# nguyen_ly.net
KiCad netlist of a schematic drawn in Altium Designer
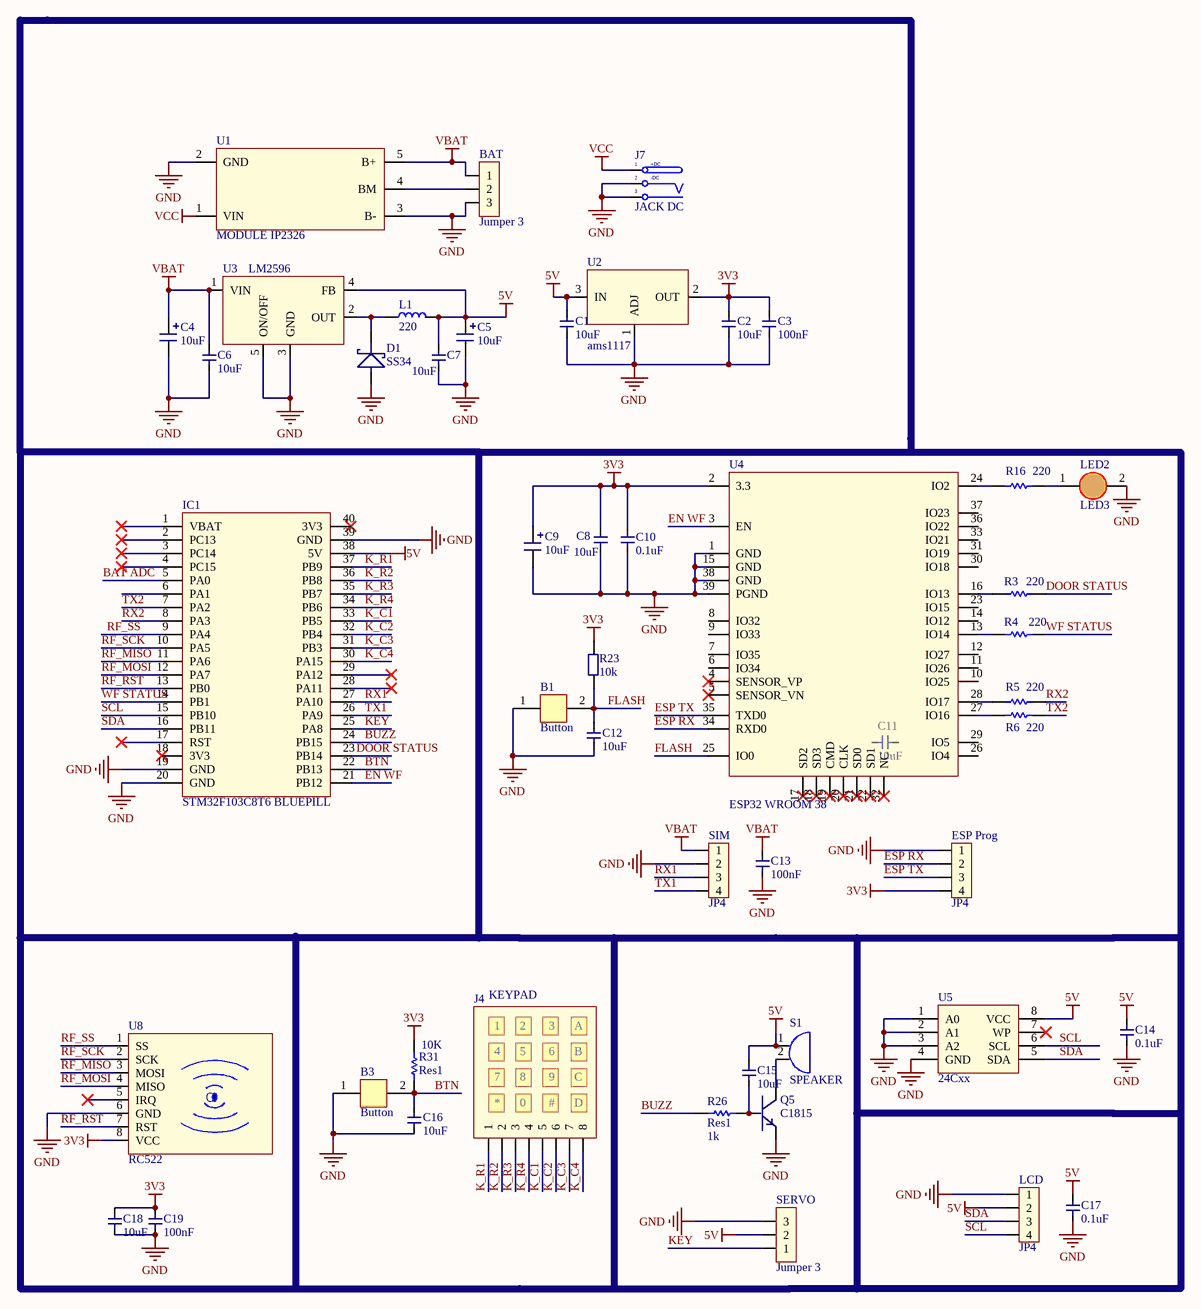
[diagram p0: nguyen_ly.SchDoc]

(export (version "E")
  (design (tool "Eeschema 10.0.6"))
  (components
    (comp (ref "B1")
      (value "Button")
      (footprint "Button 2 Pin")
      (description "Button 2 pin")
      (libsource (lib "Cty1") (part "Button 2 Pin"))
    )
    (comp (ref "B3")
      (value "Button")
      (footprint "Button 2 Pin")
      (description "Button 2 pin")
      (libsource (lib "Cty1") (part "Button 2 Pin"))
    )
    (comp (ref "BAT") (value "Jumper 3") (footprint "JP3") (libsource (lib "") (part "JP3_1")))
    (comp (ref "C1") (value "10uF") (footprint "cap 0805") (libsource (lib "Schlib1") (part "cap")))
    (comp (ref "C2") (value "10uF") (footprint "cap 0805") (libsource (lib "Schlib1") (part "cap")))
    (comp (ref "C3") (value "100nF") (footprint "cap 0805") (libsource (lib "Schlib1") (part "cap")))
    (comp (ref "C4") (value "10uF") (footprint "cap pol 63x54") (libsource (lib "Schlib1") (part "cap pol")))
    (comp (ref "C5") (value "10uF") (footprint "cap pol 63x54") (libsource (lib "Schlib1") (part "cap pol")))
    (comp (ref "C6") (value "10uF") (footprint "cap 0805") (libsource (lib "Schlib1") (part "cap")))
    (comp (ref "C7") (value "10uF") (footprint "cap 0805") (libsource (lib "Schlib1") (part "cap")))
    (comp (ref "C8") (value "10uF") (footprint "cap 0805") (libsource (lib "Schlib1") (part "cap")))
    (comp (ref "C9") (value "10uF") (footprint "cap pol 63x54") (libsource (lib "Schlib1") (part "cap pol")))
    (comp (ref "C10") (value "0.1uF") (footprint "cap 0805") (libsource (lib "Schlib1") (part "cap")))
    (comp (ref "C11") (value "10uF") (footprint "cap 0805") (libsource (lib "Schlib1") (part "cap")))
    (comp (ref "C12") (value "10uF") (footprint "cap 0805") (libsource (lib "Schlib1") (part "cap")))
    (comp (ref "C13") (value "100nF") (footprint "cap 0805") (libsource (lib "Schlib1") (part "cap")))
    (comp (ref "C14") (value "0.1uF") (footprint "cap 0805") (libsource (lib "Schlib1") (part "cap")))
    (comp (ref "C15") (value "10uF") (footprint "cap 0805") (libsource (lib "Schlib1") (part "cap")))
    (comp (ref "C16") (value "10uF") (footprint "cap 0805") (libsource (lib "Schlib1") (part "cap")))
    (comp (ref "C17") (value "0.1uF") (footprint "cap 0805") (libsource (lib "Schlib1") (part "cap")))
    (comp (ref "C18") (value "10uF") (footprint "cap 0805") (libsource (lib "Schlib1") (part "cap")))
    (comp (ref "C19") (value "100nF") (footprint "cap 0805") (libsource (lib "Schlib1") (part "cap")))
    (comp (ref "D1") (value "SS34") (footprint "Diode SS34") (libsource (lib "Schlib1") (part "SS34")))
    (comp (ref "ESP Prog") (value "JP4") (footprint "JP4") (libsource (lib "Schlib1") (part "JP4")))
    (comp (ref "IC1")
      (value "STM32F103C8T6 BLUEPILL")
      (footprint "STM32 BLUEPILL")
      (libsource (lib "Schlib1") (part "STM32F103C8T6 BLUEPILL"))
    )
    (comp (ref "J4") (value "KEYPAD") (footprint "JP8") (libsource (lib "Schlib1") (part "KEYPAD")))
    (comp (ref "J7") (value "JACK DC") (footprint "JACK DC") (libsource (lib "Schlib1") (part "JACK DC")))
    (comp (ref "L1") (value "220") (footprint "ind 74") (libsource (lib "Schlib1") (part "INDUCTOR")))
    (comp (ref "LCD") (value "JP4") (footprint "JP4") (libsource (lib "Schlib1") (part "JP4")))
    (comp (ref "LED2")
      (value "LED3")
      (footprint "LED3mm")
      (description "LED 3mm")
      (libsource (lib "Cty1") (part "LED 3mm"))
    )
    (comp (ref "Q5") (value "C1815") (footprint "Trans SOT23") (libsource (lib "Schlib1") (part "C1815 smd")))
    (comp (ref "R3")
      (value "220")
      (footprint "res 1/4w")
      (description "Resistor")
      (fields (field (name "PUBLISHER") "Altium Limited"))
      (libsource (lib "Miscellaneous Devices") (part "Res1"))
    )
    (comp (ref "R4")
      (value "220")
      (footprint "res 1/4w")
      (description "Resistor")
      (fields (field (name "PUBLISHER") "Altium Limited"))
      (libsource (lib "Miscellaneous Devices") (part "Res1"))
    )
    (comp (ref "R5")
      (value "220")
      (footprint "res 1/4w")
      (description "Resistor")
      (fields (field (name "PUBLISHER") "Altium Limited"))
      (libsource (lib "Miscellaneous Devices") (part "Res1"))
    )
    (comp (ref "R6")
      (value "220")
      (footprint "res 1/4w")
      (description "Resistor")
      (fields (field (name "PUBLISHER") "Altium Limited"))
      (libsource (lib "Miscellaneous Devices") (part "Res1"))
    )
    (comp (ref "R16")
      (value "220")
      (footprint "res 1/4w")
      (description "Resistor")
      (fields (field (name "PUBLISHER") "Altium Limited"))
      (libsource (lib "Miscellaneous Devices") (part "Res1"))
    )
    (comp (ref "R23") (value "10k") (footprint "Res 0805") (libsource (lib "Schlib1") (part "res")))
    (comp (ref "R26")
      (value "Res1")
      (footprint "res 1/4w")
      (description "Resistor")
      (fields (field (name "ALTIUM_VALUE") "1k") (field (name "PUBLISHER") "Altium Limited"))
      (libsource (lib "Miscellaneous Devices") (part "Res1"))
    )
    (comp (ref "R31")
      (value "Res1")
      (footprint "res 1/4w")
      (description "Resistor")
      (fields (field (name "ALTIUM_VALUE") "10K") (field (name "PUBLISHER") "Altium Limited"))
      (libsource (lib "Miscellaneous Devices") (part "Res1"))
    )
    (comp (ref "S1") (value "SPEAKER") (footprint "SPEAKER") (libsource (lib "Schlib1") (part "SPEAKER")))
    (comp (ref "SERVO") (value "Jumper 3") (footprint "JP3") (libsource (lib "Cty1") (part "JP3")))
    (comp (ref "SIM") (value "JP4") (footprint "JP4") (libsource (lib "Schlib1") (part "JP4")))
    (comp (ref "U1")
      (value "MODULE IP2326")
      (footprint "MACHSACPIN")
      (libsource (lib "Schlib1") (part "MACHSACPIN"))
    )
    (comp (ref "U2")
      (value "ams1117")
      (footprint "ams1117 SOT223")
      (libsource (lib "Schlib1") (part "ams1117"))
    )
    (comp (ref "U3") (value "LM2596") (footprint "LM2596") (libsource (lib "Schlib1") (part "LM2596")))
    (comp (ref "U4")
      (value "ESP32 WROOM 38")
      (footprint "ESP32 WROOM 38")
      (libsource (lib "Schlib1") (part "ESP32 WROOM 38"))
    )
    (comp (ref "U5") (value "24Cxx") (footprint "DIP8") (libsource (lib "Schlib1") (part "24Cxx")))
    (comp (ref "U8") (value "RC522") (footprint "JP8") (libsource (lib "Schlib1") (part "RC522")))
  )
  (nets
    (net (code "1") (name "/BAT ADC") (class "Default")
      (node (ref "IC1") (pin "5") (pinfunction "PA0_5") (pintype "passive"))
    )
    (net (code "2") (name "/BTN") (class "Default")
      (node (ref "B3") (pin "2") (pinfunction "2_2") (pintype "passive"))
      (node (ref "C16") (pin "2") (pinfunction "2_2") (pintype "passive"))
      (node (ref "IC1") (pin "22") (pinfunction "PB13_22") (pintype "passive"))
      (node (ref "R31") (pin "2") (pinfunction "2_2") (pintype "passive"))
    )
    (net (code "3") (name "/BUZZ") (class "Default")
      (node (ref "IC1") (pin "24") (pinfunction "PB15_24") (pintype "passive"))
      (node (ref "R26") (pin "1") (pinfunction "1_1") (pintype "passive"))
    )
    (net (code "4") (name "/DOOR STATUS") (class "Default")
      (node (ref "IC1") (pin "23") (pinfunction "PB14_23") (pintype "passive"))
      (node (ref "R3") (pin "1") (pinfunction "1_1") (pintype "passive"))
    )
    (net (code "5") (name "/EN WF") (class "Default")
      (node (ref "IC1") (pin "21") (pinfunction "PB12_21") (pintype "passive"))
      (node (ref "U4") (pin "3") (pinfunction "EN_3") (pintype "passive"))
    )
    (net (code "6") (name "/ESP RX") (class "Default")
      (node (ref "ESP Prog") (pin "2") (pinfunction "2_2") (pintype "passive"))
      (node (ref "U4") (pin "34") (pinfunction "RXD0_34") (pintype "passive"))
    )
    (net (code "7") (name "/ESP TX") (class "Default")
      (node (ref "ESP Prog") (pin "3") (pinfunction "3_3") (pintype "passive"))
      (node (ref "U4") (pin "35") (pinfunction "TXD0_35") (pintype "passive"))
    )
    (net (code "8") (name "/FLASH") (class "Default")
      (node (ref "B1") (pin "2") (pinfunction "2_2") (pintype "passive"))
      (node (ref "C12") (pin "2") (pinfunction "2_2") (pintype "passive"))
      (node (ref "R23") (pin "1") (pinfunction "1_1") (pintype "passive"))
      (node (ref "U4") (pin "25") (pinfunction "IO0_25") (pintype "passive"))
    )
    (net (code "9") (name "/KEY") (class "Default")
      (node (ref "IC1") (pin "25") (pinfunction "PA8_25") (pintype "passive"))
      (node (ref "SERVO") (pin "1") (pinfunction "1_1") (pintype "passive"))
    )
    (net (code "10") (name "/K_C1") (class "Default")
      (node (ref "IC1") (pin "33") (pinfunction "PB5_33") (pintype "passive"))
      (node (ref "J4") (pin "5") (pinfunction "5_5") (pintype "passive"))
    )
    (net (code "11") (name "/K_C2") (class "Default")
      (node (ref "IC1") (pin "32") (pinfunction "PB4_32") (pintype "passive"))
      (node (ref "J4") (pin "6") (pinfunction "6_6") (pintype "passive"))
    )
    (net (code "12") (name "/K_C3") (class "Default")
      (node (ref "IC1") (pin "31") (pinfunction "PB3_31") (pintype "passive"))
      (node (ref "J4") (pin "7") (pinfunction "7_7") (pintype "passive"))
    )
    (net (code "13") (name "/K_C4") (class "Default")
      (node (ref "IC1") (pin "30") (pinfunction "PA15_30") (pintype "passive"))
      (node (ref "J4") (pin "8") (pinfunction "8_8") (pintype "passive"))
    )
    (net (code "14") (name "/K_R1") (class "Default")
      (node (ref "IC1") (pin "37") (pinfunction "PB9_37") (pintype "passive"))
      (node (ref "J4") (pin "1") (pinfunction "1_1") (pintype "passive"))
    )
    (net (code "15") (name "/K_R2") (class "Default")
      (node (ref "IC1") (pin "36") (pinfunction "PB8_36") (pintype "passive"))
      (node (ref "J4") (pin "2") (pinfunction "2_2") (pintype "passive"))
    )
    (net (code "16") (name "/K_R3") (class "Default")
      (node (ref "IC1") (pin "35") (pinfunction "PB7_35") (pintype "passive"))
      (node (ref "J4") (pin "3") (pinfunction "3_3") (pintype "passive"))
    )
    (net (code "17") (name "/K_R4") (class "Default")
      (node (ref "IC1") (pin "34") (pinfunction "PB6_34") (pintype "passive"))
      (node (ref "J4") (pin "4") (pinfunction "4_4") (pintype "passive"))
    )
    (net (code "18") (name "/RF_MISO") (class "Default")
      (node (ref "IC1") (pin "11") (pinfunction "PA6_11") (pintype "passive"))
      (node (ref "U8") (pin "3") (pinfunction "MOSI_3") (pintype "passive"))
    )
    (net (code "19") (name "/RF_MOSI") (class "Default")
      (node (ref "IC1") (pin "12") (pinfunction "PA7_12") (pintype "passive"))
      (node (ref "U8") (pin "4") (pinfunction "MISO_4") (pintype "passive"))
    )
    (net (code "20") (name "/RF_RST") (class "Default")
      (node (ref "IC1") (pin "13") (pinfunction "PB0_13") (pintype "passive"))
      (node (ref "U8") (pin "7") (pinfunction "RST_7") (pintype "passive"))
    )
    (net (code "21") (name "/RF_SCK") (class "Default")
      (node (ref "IC1") (pin "10") (pinfunction "PA5_10") (pintype "passive"))
      (node (ref "U8") (pin "2") (pinfunction "SCK_2") (pintype "passive"))
    )
    (net (code "22") (name "/RF_SS") (class "Default")
      (node (ref "IC1") (pin "9") (pinfunction "PA4_9") (pintype "passive"))
      (node (ref "U8") (pin "1") (pinfunction "SS_1") (pintype "passive"))
    )
    (net (code "23") (name "/RX1") (class "Default")
      (node (ref "IC1") (pin "27") (pinfunction "PA10_27") (pintype "passive"))
      (node (ref "SIM") (pin "3") (pinfunction "3_3") (pintype "passive"))
    )
    (net (code "24") (name "/RX2") (class "Default")
      (node (ref "IC1") (pin "8") (pinfunction "PA3_8") (pintype "passive"))
      (node (ref "R5") (pin "1") (pinfunction "1_1") (pintype "passive"))
    )
    (net (code "25") (name "/SCL") (class "Default")
      (node (ref "IC1") (pin "15") (pinfunction "PB10_15") (pintype "passive"))
      (node (ref "LCD") (pin "4") (pinfunction "4_4") (pintype "passive"))
      (node (ref "U5") (pin "6") (pinfunction "SCL_6") (pintype "passive"))
    )
    (net (code "26") (name "/SDA") (class "Default")
      (node (ref "IC1") (pin "16") (pinfunction "PB11_16") (pintype "passive"))
      (node (ref "LCD") (pin "3") (pinfunction "3_3") (pintype "passive"))
      (node (ref "U5") (pin "5") (pinfunction "SDA_5") (pintype "passive"))
    )
    (net (code "27") (name "/TX1") (class "Default")
      (node (ref "IC1") (pin "26") (pinfunction "PA9_26") (pintype "passive"))
      (node (ref "SIM") (pin "4") (pinfunction "4_4") (pintype "passive"))
    )
    (net (code "28") (name "/TX2") (class "Default")
      (node (ref "IC1") (pin "7") (pinfunction "PA2_7") (pintype "passive"))
      (node (ref "R6") (pin "1") (pinfunction "1_1") (pintype "passive"))
    )
    (net (code "29") (name "/WF STATUS") (class "Default")
      (node (ref "IC1") (pin "14") (pinfunction "PB1_14") (pintype "passive"))
      (node (ref "R4") (pin "1") (pinfunction "1_1") (pintype "passive"))
    )
    (net (code "30") (name "3V3") (class "Default")
      (node (ref "C10") (pin "2") (pinfunction "2_2") (pintype "passive"))
      (node (ref "C18") (pin "2") (pinfunction "2_2") (pintype "passive"))
      (node (ref "C19") (pin "2") (pinfunction "2_2") (pintype "passive"))
      (node (ref "C2") (pin "2") (pinfunction "2_2") (pintype "passive"))
      (node (ref "C3") (pin "2") (pinfunction "2_2") (pintype "passive"))
      (node (ref "C8") (pin "2") (pinfunction "2_2") (pintype "passive"))
      (node (ref "C9") (pin "1") (pinfunction "1_1") (pintype "passive"))
      (node (ref "ESP Prog") (pin "4") (pinfunction "4_4") (pintype "passive"))
      (node (ref "R23") (pin "2") (pinfunction "2_2") (pintype "passive"))
      (node (ref "R31") (pin "1") (pinfunction "1_1") (pintype "passive"))
      (node (ref "U2") (pin "2") (pinfunction "OUT_2") (pintype "passive"))
      (node (ref "U4") (pin "2") (pinfunction "3.3_2") (pintype "passive"))
      (node (ref "U8") (pin "8") (pinfunction "VCC_8") (pintype "passive"))
    )
    (net (code "31") (name "5V") (class "Default")
      (node (ref "C1") (pin "2") (pinfunction "2_2") (pintype "passive"))
      (node (ref "C14") (pin "2") (pinfunction "2_2") (pintype "passive"))
      (node (ref "C15") (pin "2") (pinfunction "2_2") (pintype "passive"))
      (node (ref "C17") (pin "2") (pinfunction "2_2") (pintype "passive"))
      (node (ref "C5") (pin "1") (pinfunction "1_1") (pintype "passive"))
      (node (ref "C7") (pin "2") (pinfunction "2_2") (pintype "passive"))
      (node (ref "IC1") (pin "38") (pinfunction "5V_38") (pintype "passive"))
      (node (ref "L1") (pin "2") (pinfunction "2_2") (pintype "passive"))
      (node (ref "LCD") (pin "2") (pinfunction "2_2") (pintype "passive"))
      (node (ref "S1") (pin "1") (pinfunction "A_1") (pintype "passive"))
      (node (ref "SERVO") (pin "2") (pinfunction "2_2") (pintype "passive"))
      (node (ref "U2") (pin "3") (pinfunction "IN_3") (pintype "passive"))
      (node (ref "U3") (pin "4") (pinfunction "FB_4") (pintype "passive"))
      (node (ref "U5") (pin "8") (pinfunction "VCC_8") (pintype "power_in"))
    )
    (net (code "32") (name "GND") (class "Default")
      (node (ref "B1") (pin "1") (pinfunction "1_1") (pintype "passive"))
      (node (ref "B3") (pin "1") (pinfunction "1_1") (pintype "passive"))
      (node (ref "BAT") (pin "3") (pinfunction "3_3") (pintype "passive"))
      (node (ref "C1") (pin "1") (pinfunction "1_1") (pintype "passive"))
      (node (ref "C10") (pin "1") (pinfunction "1_1") (pintype "passive"))
      (node (ref "C12") (pin "1") (pinfunction "1_1") (pintype "passive"))
      (node (ref "C13") (pin "1") (pinfunction "1_1") (pintype "passive"))
      (node (ref "C14") (pin "1") (pinfunction "1_1") (pintype "passive"))
      (node (ref "C16") (pin "1") (pinfunction "1_1") (pintype "passive"))
      (node (ref "C17") (pin "1") (pinfunction "1_1") (pintype "passive"))
      (node (ref "C18") (pin "1") (pinfunction "1_1") (pintype "passive"))
      (node (ref "C19") (pin "1") (pinfunction "1_1") (pintype "passive"))
      (node (ref "C2") (pin "1") (pinfunction "1_1") (pintype "passive"))
      (node (ref "C3") (pin "1") (pinfunction "1_1") (pintype "passive"))
      (node (ref "C4") (pin "2") (pinfunction "2_2") (pintype "passive"))
      (node (ref "C5") (pin "2") (pinfunction "2_2") (pintype "passive"))
      (node (ref "C6") (pin "1") (pinfunction "1_1") (pintype "passive"))
      (node (ref "C7") (pin "1") (pinfunction "1_1") (pintype "passive"))
      (node (ref "C8") (pin "1") (pinfunction "1_1") (pintype "passive"))
      (node (ref "C9") (pin "2") (pinfunction "2_2") (pintype "passive"))
      (node (ref "D1") (pin "1") (pinfunction "1_1") (pintype "passive"))
      (node (ref "ESP Prog") (pin "1") (pinfunction "1_1") (pintype "passive"))
      (node (ref "IC1") (pin "19") (pinfunction "GND_19") (pintype "passive"))
      (node (ref "IC1") (pin "20") (pinfunction "GND_20") (pintype "passive"))
      (node (ref "IC1") (pin "39") (pinfunction "GND_39") (pintype "passive"))
      (node (ref "J7") (pin "2") (pinfunction "TN_2") (pintype "passive"))
      (node (ref "J7") (pin "3") (pinfunction "S_3") (pintype "power_in"))
      (node (ref "LCD") (pin "1") (pinfunction "1_1") (pintype "passive"))
      (node (ref "LED2") (pin "2") (pinfunction "K_2") (pintype "passive"))
      (node (ref "Q5") (pin "2") (pinfunction "E_2") (pintype "passive"))
      (node (ref "SERVO") (pin "3") (pinfunction "3_3") (pintype "passive"))
      (node (ref "SIM") (pin "2") (pinfunction "2_2") (pintype "passive"))
      (node (ref "U1") (pin "2") (pinfunction "GND_2") (pintype "passive"))
      (node (ref "U1") (pin "3") (pinfunction "B-_3") (pintype "passive"))
      (node (ref "U2") (pin "1") (pinfunction "ADJ_1") (pintype "passive"))
      (node (ref "U3") (pin "3") (pinfunction "GND_3") (pintype "passive"))
      (node (ref "U3") (pin "5") (pinfunction "ON/OFF_5") (pintype "passive"))
      (node (ref "U4") (pin "1") (pinfunction "GND_1") (pintype "passive"))
      (node (ref "U4") (pin "15") (pinfunction "GND_15") (pintype "passive"))
      (node (ref "U4") (pin "38") (pinfunction "GND_38") (pintype "passive"))
      (node (ref "U4") (pin "39") (pinfunction "PGND_39") (pintype "passive"))
      (node (ref "U5") (pin "1") (pinfunction "A0_1") (pintype "passive"))
      (node (ref "U5") (pin "2") (pinfunction "A1_2") (pintype "passive"))
      (node (ref "U5") (pin "3") (pinfunction "A2_3") (pintype "passive"))
      (node (ref "U5") (pin "4") (pinfunction "GND_4") (pintype "power_in"))
      (node (ref "U8") (pin "6") (pinfunction "GND_6") (pintype "passive"))
    )
    (net (code "33") (name "Net-(LED2-A)") (class "Default")
      (node (ref "LED2") (pin "1") (pinfunction "A_1") (pintype "passive"))
      (node (ref "R16") (pin "1") (pinfunction "1_1") (pintype "passive"))
    )
    (net (code "34") (name "Net-(Q5-B)") (class "Default")
      (node (ref "C15") (pin "1") (pinfunction "1_1") (pintype "passive"))
      (node (ref "Q5") (pin "1") (pinfunction "B_1") (pintype "passive"))
      (node (ref "R26") (pin "2") (pinfunction "2_2") (pintype "passive"))
    )
    (net (code "35") (name "Net-(Q5-C)") (class "Default")
      (node (ref "Q5") (pin "3") (pinfunction "C_3") (pintype "passive"))
      (node (ref "S1") (pin "2") (pinfunction "B_2") (pintype "passive"))
    )
    (net (code "36") (name "Net-(U1-BM)") (class "Default")
      (node (ref "BAT") (pin "2") (pinfunction "2_2") (pintype "passive"))
      (node (ref "U1") (pin "4") (pinfunction "BM_4") (pintype "passive"))
    )
    (net (code "37") (name "Net-(U3-OUT)") (class "Default")
      (node (ref "D1") (pin "2") (pinfunction "2_2") (pintype "passive"))
      (node (ref "L1") (pin "1") (pinfunction "1_1") (pintype "passive"))
      (node (ref "U3") (pin "2") (pinfunction "OUT_2") (pintype "passive"))
    )
    (net (code "38") (name "Net-(U4-IO2)") (class "Default")
      (node (ref "R16") (pin "2") (pinfunction "2_2") (pintype "passive"))
      (node (ref "U4") (pin "24") (pinfunction "IO2_24") (pintype "passive"))
    )
    (net (code "39") (name "Net-(U4-IO13)") (class "Default")
      (node (ref "R3") (pin "2") (pinfunction "2_2") (pintype "passive"))
      (node (ref "U4") (pin "16") (pinfunction "IO13_16") (pintype "passive"))
    )
    (net (code "40") (name "Net-(U4-IO14)") (class "Default")
      (node (ref "R4") (pin "2") (pinfunction "2_2") (pintype "passive"))
      (node (ref "U4") (pin "13") (pinfunction "IO14_13") (pintype "passive"))
    )
    (net (code "41") (name "Net-(U4-IO16)") (class "Default")
      (node (ref "R6") (pin "2") (pinfunction "2_2") (pintype "passive"))
      (node (ref "U4") (pin "27") (pinfunction "IO16_27") (pintype "passive"))
    )
    (net (code "42") (name "Net-(U4-IO17)") (class "Default")
      (node (ref "R5") (pin "2") (pinfunction "2_2") (pintype "passive"))
      (node (ref "U4") (pin "28") (pinfunction "IO17_28") (pintype "passive"))
    )
    (net (code "43") (name "VBAT") (class "Default")
      (node (ref "BAT") (pin "1") (pinfunction "1_1") (pintype "passive"))
      (node (ref "C13") (pin "2") (pinfunction "2_2") (pintype "passive"))
      (node (ref "C4") (pin "1") (pinfunction "1_1") (pintype "passive"))
      (node (ref "C6") (pin "2") (pinfunction "2_2") (pintype "passive"))
      (node (ref "SIM") (pin "1") (pinfunction "1_1") (pintype "passive"))
      (node (ref "U1") (pin "5") (pinfunction "B+_5") (pintype "passive"))
      (node (ref "U3") (pin "1") (pinfunction "VIN_1") (pintype "passive"))
    )
    (net (code "44") (name "VCC") (class "Default")
      (node (ref "J7") (pin "1") (pinfunction "T_1") (pintype "passive"))
      (node (ref "U1") (pin "1") (pinfunction "VIN_1") (pintype "passive"))
    )
    (net (code "45") (name "unconnected-(C11-Pad1)") (class "Default")
      (node (ref "C11") (pin "1") (pinfunction "1_1") (pintype "passive"))
    )
    (net (code "46") (name "unconnected-(C11-Pad2)") (class "Default")
      (node (ref "C11") (pin "2") (pinfunction "2_2") (pintype "passive"))
    )
    (net (code "47") (name "unconnected-(IC1-3V3-Pad18)") (class "Default")
      (node (ref "IC1") (pin "18") (pinfunction "3V3_18") (pintype "passive+no_connect"))
    )
    (net (code "48") (name "unconnected-(IC1-3V3-Pad40)") (class "Default")
      (node (ref "IC1") (pin "40") (pinfunction "3V3_40") (pintype "passive+no_connect"))
    )
    (net (code "49") (name "unconnected-(IC1-PA1-Pad6)") (class "Default")
      (node (ref "IC1") (pin "6") (pinfunction "PA1_6") (pintype "passive"))
    )
    (net (code "50") (name "unconnected-(IC1-PA11-Pad28)") (class "Default")
      (node (ref "IC1") (pin "28") (pinfunction "PA11_28") (pintype "passive+no_connect"))
    )
    (net (code "51") (name "unconnected-(IC1-PA12-Pad29)") (class "Default")
      (node (ref "IC1") (pin "29") (pinfunction "PA12_29") (pintype "passive+no_connect"))
    )
    (net (code "52") (name "unconnected-(IC1-PC13-Pad2)") (class "Default")
      (node (ref "IC1") (pin "2") (pinfunction "PC13_2") (pintype "passive+no_connect"))
    )
    (net (code "53") (name "unconnected-(IC1-PC14-Pad3)") (class "Default")
      (node (ref "IC1") (pin "3") (pinfunction "PC14_3") (pintype "passive+no_connect"))
    )
    (net (code "54") (name "unconnected-(IC1-PC15-Pad4)") (class "Default")
      (node (ref "IC1") (pin "4") (pinfunction "PC15_4") (pintype "passive+no_connect"))
    )
    (net (code "55") (name "unconnected-(IC1-RST-Pad17)") (class "Default")
      (node (ref "IC1") (pin "17") (pinfunction "RST_17") (pintype "passive+no_connect"))
    )
    (net (code "56") (name "unconnected-(IC1-VBAT-Pad1)") (class "Default")
      (node (ref "IC1") (pin "1") (pinfunction "VBAT_1") (pintype "passive+no_connect"))
    )
    (net (code "57") (name "unconnected-(U4-CLK-Pad20)") (class "Default")
      (node (ref "U4") (pin "20") (pinfunction "CLK_20") (pintype "passive+no_connect"))
    )
    (net (code "58") (name "unconnected-(U4-CMD-Pad19)") (class "Default")
      (node (ref "U4") (pin "19") (pinfunction "CMD_19") (pintype "passive+no_connect"))
    )
    (net (code "59") (name "unconnected-(U4-IO4-Pad26)") (class "Default")
      (node (ref "U4") (pin "26") (pinfunction "IO4_26") (pintype "passive"))
    )
    (net (code "60") (name "unconnected-(U4-IO5-Pad29)") (class "Default")
      (node (ref "U4") (pin "29") (pinfunction "IO5_29") (pintype "passive"))
    )
    (net (code "61") (name "unconnected-(U4-IO12-Pad14)") (class "Default")
      (node (ref "U4") (pin "14") (pinfunction "IO12_14") (pintype "passive"))
    )
    (net (code "62") (name "unconnected-(U4-IO15-Pad23)") (class "Default")
      (node (ref "U4") (pin "23") (pinfunction "IO15_23") (pintype "passive"))
    )
    (net (code "63") (name "unconnected-(U4-IO18-Pad30)") (class "Default")
      (node (ref "U4") (pin "30") (pinfunction "IO18_30") (pintype "passive"))
    )
    (net (code "64") (name "unconnected-(U4-IO19-Pad31)") (class "Default")
      (node (ref "U4") (pin "31") (pinfunction "IO19_31") (pintype "passive"))
    )
    (net (code "65") (name "unconnected-(U4-IO21-Pad33)") (class "Default")
      (node (ref "U4") (pin "33") (pinfunction "IO21_33") (pintype "passive"))
    )
    (net (code "66") (name "unconnected-(U4-IO22-Pad36)") (class "Default")
      (node (ref "U4") (pin "36") (pinfunction "IO22_36") (pintype "passive"))
    )
    (net (code "67") (name "unconnected-(U4-IO23-Pad37)") (class "Default")
      (node (ref "U4") (pin "37") (pinfunction "IO23_37") (pintype "passive"))
    )
    (net (code "68") (name "unconnected-(U4-IO25-Pad10)") (class "Default")
      (node (ref "U4") (pin "10") (pinfunction "IO25_10") (pintype "passive"))
    )
    (net (code "69") (name "unconnected-(U4-IO26-Pad11)") (class "Default")
      (node (ref "U4") (pin "11") (pinfunction "IO26_11") (pintype "passive"))
    )
    (net (code "70") (name "unconnected-(U4-IO27-Pad12)") (class "Default")
      (node (ref "U4") (pin "12") (pinfunction "IO27_12") (pintype "passive"))
    )
    (net (code "71") (name "unconnected-(U4-IO32-Pad8)") (class "Default")
      (node (ref "U4") (pin "8") (pinfunction "IO32_8") (pintype "passive"))
    )
    (net (code "72") (name "unconnected-(U4-IO33-Pad9)") (class "Default")
      (node (ref "U4") (pin "9") (pinfunction "IO33_9") (pintype "passive"))
    )
    (net (code "73") (name "unconnected-(U4-IO34-Pad6)") (class "Default")
      (node (ref "U4") (pin "6") (pinfunction "IO34_6") (pintype "passive"))
    )
    (net (code "74") (name "unconnected-(U4-IO35-Pad7)") (class "Default")
      (node (ref "U4") (pin "7") (pinfunction "IO35_7") (pintype "passive"))
    )
    (net (code "75") (name "unconnected-(U4-NC-Pad32)") (class "Default")
      (node (ref "U4") (pin "32") (pinfunction "NC_32") (pintype "passive+no_connect"))
    )
    (net (code "76") (name "unconnected-(U4-SD0-Pad21)") (class "Default")
      (node (ref "U4") (pin "21") (pinfunction "SD0_21") (pintype "passive+no_connect"))
    )
    (net (code "77") (name "unconnected-(U4-SD1-Pad22)") (class "Default")
      (node (ref "U4") (pin "22") (pinfunction "SD1_22") (pintype "passive+no_connect"))
    )
    (net (code "78") (name "unconnected-(U4-SD2-Pad17)") (class "Default")
      (node (ref "U4") (pin "17") (pinfunction "SD2_17") (pintype "passive+no_connect"))
    )
    (net (code "79") (name "unconnected-(U4-SD3-Pad18)") (class "Default")
      (node (ref "U4") (pin "18") (pinfunction "SD3_18") (pintype "passive+no_connect"))
    )
    (net (code "80") (name "unconnected-(U4-SENSOR_VN-Pad5)") (class "Default")
      (node (ref "U4") (pin "5") (pinfunction "SENSOR_VN_5") (pintype "passive+no_connect"))
    )
    (net (code "81") (name "unconnected-(U4-SENSOR_VP-Pad4)") (class "Default")
      (node (ref "U4") (pin "4") (pinfunction "SENSOR_VP_4") (pintype "passive+no_connect"))
    )
    (net (code "82") (name "unconnected-(U5-WP-Pad7)") (class "Default")
      (node (ref "U5") (pin "7") (pinfunction "WP_7") (pintype "passive+no_connect"))
    )
    (net (code "83") (name "unconnected-(U8-IRQ-Pad5)") (class "Default")
      (node (ref "U8") (pin "5") (pinfunction "IRQ_5") (pintype "passive+no_connect"))
    )
  )
)
